# MainSch.net
KiCad netlist of a schematic drawn in Altium Designer
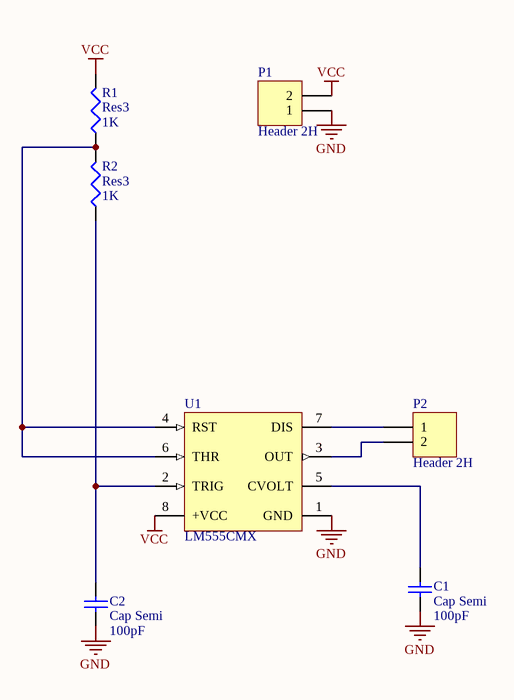
[diagram p0: MainSch.SchDoc]

(export (version "E")
  (design (tool "Eeschema 10.0.6"))
  (components
    (comp (ref "C1")
      (value "Cap Semi")
      (footprint "C1206")
      (description "Capacitor (Semiconductor SIM Model)")
      (fields (field (name "ALTIUM_VALUE") "100pF") (field (name "PUBLISHER") "Altium Limited"))
      (libsource (lib "Miscellaneous Devices") (part "Cap Semi"))
    )
    (comp (ref "C2")
      (value "Cap Semi")
      (footprint "C1206")
      (description "Capacitor (Semiconductor SIM Model)")
      (fields (field (name "ALTIUM_VALUE") "100pF") (field (name "PUBLISHER") "Altium Limited"))
      (libsource (lib "Miscellaneous Devices") (part "Cap Semi"))
    )
    (comp (ref "P1")
      (value "Header 2H")
      (footprint "HDR1X2H")
      (description "Header, 2-Pin, Right Angle")
      (fields (field (name "PUBLISHER") "Altium Limited"))
      (libsource (lib "") (part "Header 2H_1"))
    )
    (comp (ref "P2")
      (value "Header 2H")
      (footprint "HDR1X2H")
      (description "Header, 2-Pin, Right Angle")
      (fields (field (name "PUBLISHER") "Altium Limited"))
      (libsource (lib "Miscellaneous Connectors") (part "Header 2H"))
    )
    (comp (ref "R1")
      (value "Res3")
      (footprint "J1-0603")
      (description "Resistor")
      (fields (field (name "ALTIUM_VALUE") "1K") (field (name "PUBLISHER") "Altium Limited"))
      (libsource (lib "Miscellaneous Devices") (part "Res3"))
    )
    (comp (ref "R2")
      (value "Res3")
      (footprint "J1-0603")
      (description "Resistor")
      (fields (field (name "ALTIUM_VALUE") "1K") (field (name "PUBLISHER") "Altium Limited"))
      (libsource (lib "Miscellaneous Devices") (part "Res3"))
    )
    (comp (ref "U1")
      (value "LM555CMX")
      (footprint "M08A_N")
      (description "Timer, 8-pin Narrow SOIC")
      (fields
        (field (name "MANUFACTURER") "National Semiconductor")
        (field (name "PUBLISHER") "Altium Limited")
      )
      (libsource (lib "NSC Analog") (part "LM555CMX"))
    )
  )
  (nets
    (net (code "1") (name "GND") (class "Default")
      (node (ref "C1") (pin "1") (pinfunction "1_1") (pintype "passive"))
      (node (ref "C2") (pin "1") (pinfunction "1_1") (pintype "passive"))
      (node (ref "P1") (pin "1") (pinfunction "1_1") (pintype "passive"))
      (node (ref "U1") (pin "1") (pinfunction "GND_1") (pintype "power_in"))
    )
    (net (code "2") (name "Net-(U1-CVOLT)") (class "Default")
      (node (ref "C1") (pin "2") (pinfunction "2_2") (pintype "passive"))
      (node (ref "U1") (pin "5") (pinfunction "CVOLT_5") (pintype "passive"))
    )
    (net (code "3") (name "Net-(U1-DIS)") (class "Default")
      (node (ref "P2") (pin "1") (pinfunction "1_1") (pintype "passive"))
      (node (ref "U1") (pin "7") (pinfunction "DIS_7") (pintype "open_collector"))
    )
    (net (code "4") (name "Net-(U1-OUT)") (class "Default")
      (node (ref "P2") (pin "2") (pinfunction "2_2") (pintype "passive"))
      (node (ref "U1") (pin "3") (pinfunction "OUT_3") (pintype "output"))
    )
    (net (code "5") (name "Net-(U1-RST)") (class "Default")
      (node (ref "R1") (pin "1") (pinfunction "1_1") (pintype "passive"))
      (node (ref "R2") (pin "2") (pinfunction "2_2") (pintype "passive"))
      (node (ref "U1") (pin "4") (pinfunction "RST_4") (pintype "input"))
      (node (ref "U1") (pin "6") (pinfunction "THR_6") (pintype "input"))
    )
    (net (code "6") (name "Net-(U1-TRIG)") (class "Default")
      (node (ref "C2") (pin "2") (pinfunction "2_2") (pintype "passive"))
      (node (ref "R2") (pin "1") (pinfunction "1_1") (pintype "passive"))
      (node (ref "U1") (pin "2") (pinfunction "TRIG_2") (pintype "input"))
    )
    (net (code "7") (name "VCC") (class "Default")
      (node (ref "P1") (pin "2") (pinfunction "2_2") (pintype "passive"))
      (node (ref "R1") (pin "2") (pinfunction "2_2") (pintype "passive"))
      (node (ref "U1") (pin "8") (pinfunction "+VCC_8") (pintype "power_in"))
    )
  )
)
